# Soldier_Tracking.net
KiCad netlist of a schematic drawn in EAGLE
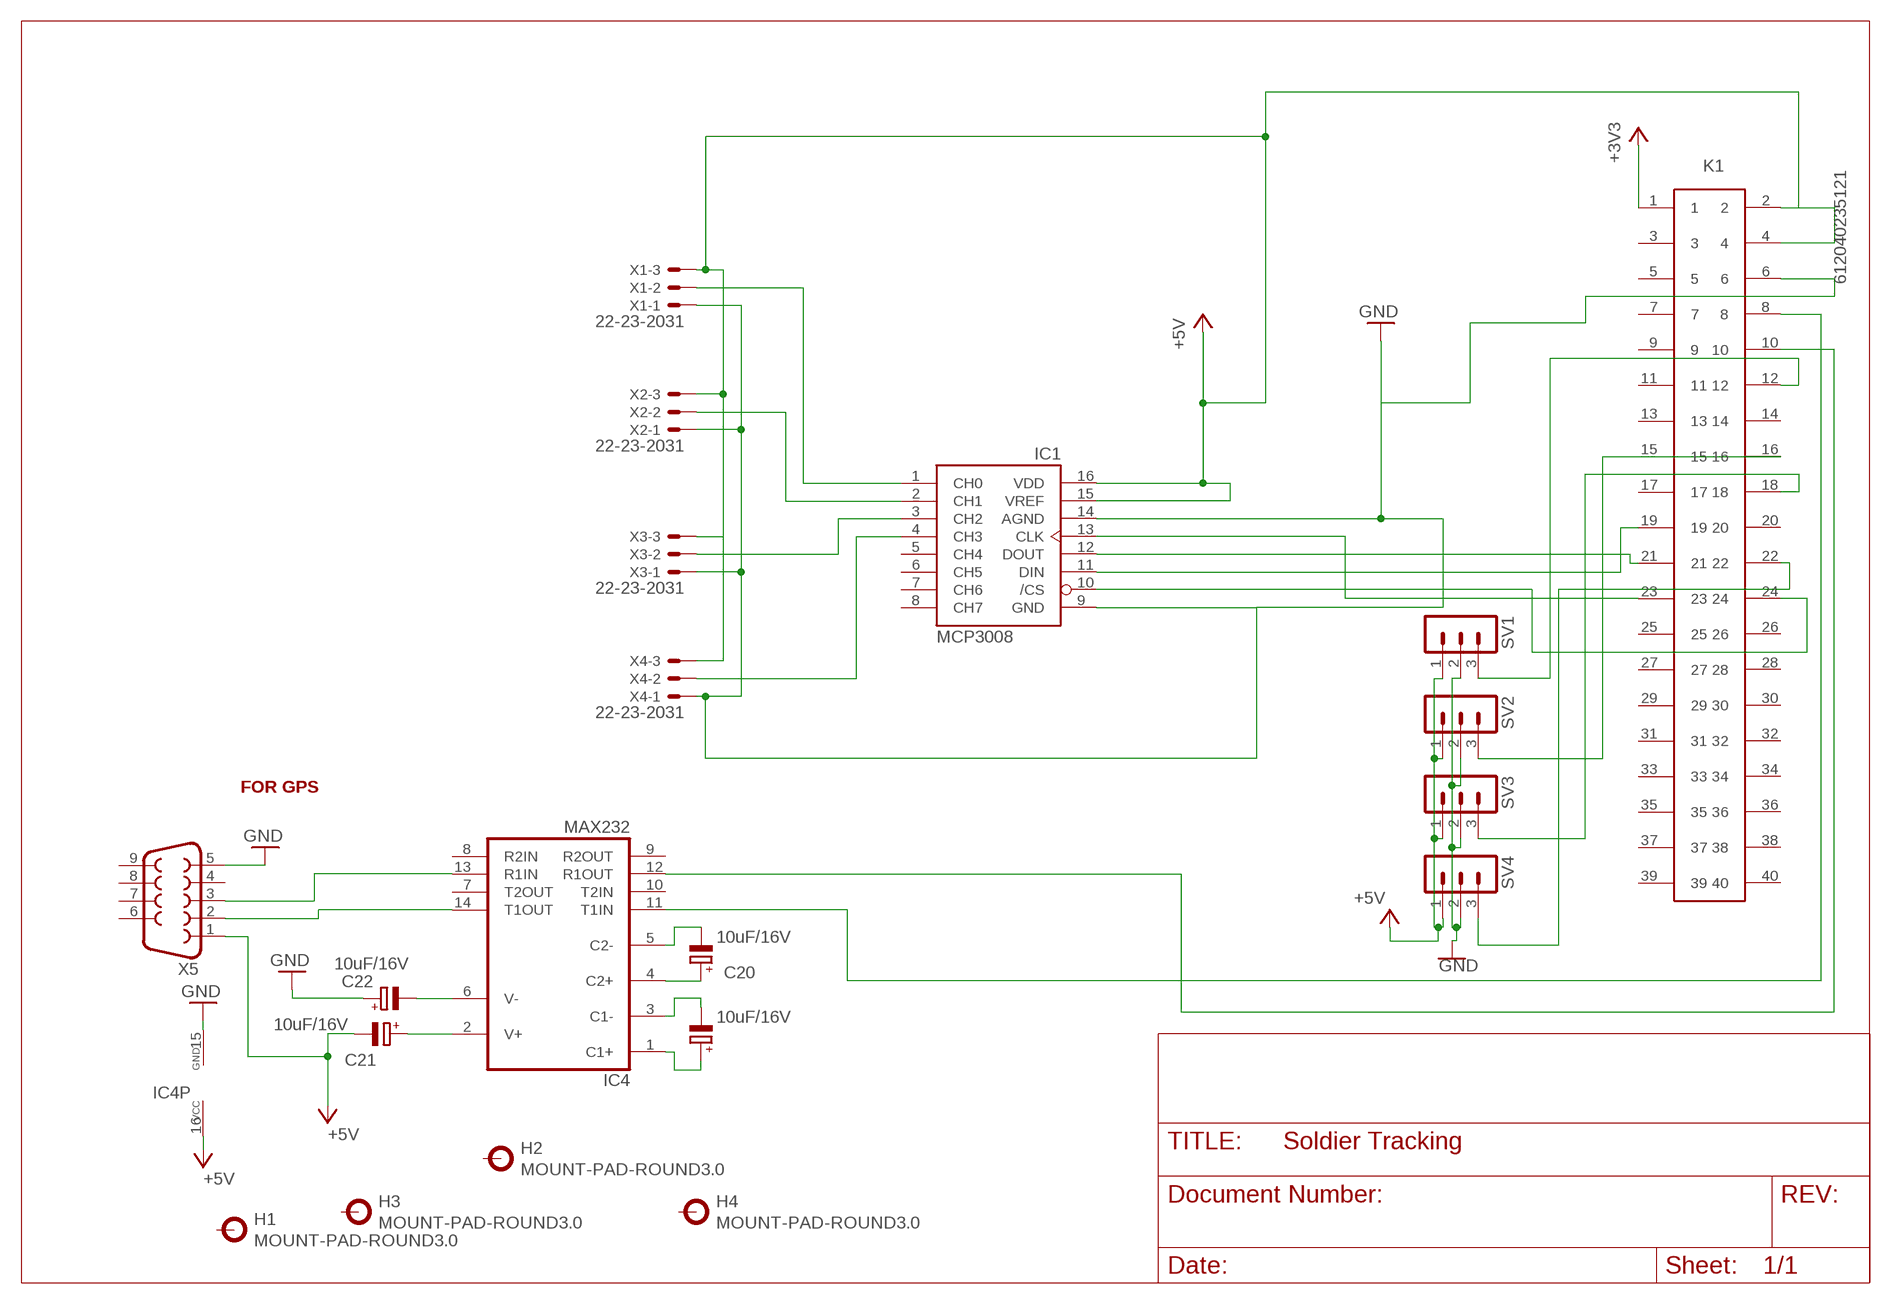
[diagram p0: schematic, sheet 1]

(export (version "E")
  (design (tool "Eeschema 10.0.6"))
  (components
    (comp (ref "C17")
      (value "10uF/16V")
      (footprint "eagle-import:E2,5-6")
      (libsource (lib "eagle-import") (part "CPOL-EUE2.5-6"))
    )
    (comp (ref "C20")
      (value "10uF/16V")
      (footprint "eagle-import:E2,5-6")
      (libsource (lib "eagle-import") (part "CPOL-EUE2.5-6"))
    )
    (comp (ref "C21")
      (value "10uF/16V")
      (footprint "eagle-import:E2,5-6")
      (libsource (lib "eagle-import") (part "CPOL-EUE2.5-6"))
    )
    (comp (ref "C22")
      (value "10uF/16V")
      (footprint "eagle-import:E2,5-6")
      (libsource (lib "eagle-import") (part "CPOL-EUE2.5-6"))
    )
    (comp (ref "H1")
      (value "MOUNT-PAD-ROUND3.0")
      (footprint "eagle-import:3,0-PAD")
      (libsource (lib "eagle-import") (part "MOUNT-PAD-ROUND3.0"))
    )
    (comp (ref "H2")
      (value "MOUNT-PAD-ROUND3.0")
      (footprint "eagle-import:3,0-PAD")
      (libsource (lib "eagle-import") (part "MOUNT-PAD-ROUND3.0"))
    )
    (comp (ref "H3")
      (value "MOUNT-PAD-ROUND3.0")
      (footprint "eagle-import:3,0-PAD")
      (libsource (lib "eagle-import") (part "MOUNT-PAD-ROUND3.0"))
    )
    (comp (ref "H4")
      (value "MOUNT-PAD-ROUND3.0")
      (footprint "eagle-import:3,0-PAD")
      (libsource (lib "eagle-import") (part "MOUNT-PAD-ROUND3.0"))
    )
    (comp (ref "IC1")
      (value "MCP3008")
      (footprint "eagle-import:DIL16")
      (libsource (lib "eagle-import") (part "MCP3008"))
    )
    (comp (ref "IC4")
      (value "MAX232")
      (footprint "eagle-import:DIL16")
      (libsource (lib "eagle-import") (part "MAX232"))
    )
    (comp (ref "K1")
      (value "612040235121")
      (footprint "eagle-import:612040235121")
      (libsource (lib "eagle-import") (part "612040235121"))
    )
    (comp (ref "SV1")
      (value "MA03-1")
      (footprint "eagle-import:MA03-1")
      (libsource (lib "eagle-import") (part "MA03-1"))
    )
    (comp (ref "SV2")
      (value "MA03-1")
      (footprint "eagle-import:MA03-1")
      (libsource (lib "eagle-import") (part "MA03-1"))
    )
    (comp (ref "SV3")
      (value "MA03-1")
      (footprint "eagle-import:MA03-1")
      (libsource (lib "eagle-import") (part "MA03-1"))
    )
    (comp (ref "SV4")
      (value "MA03-1")
      (footprint "eagle-import:MA03-1")
      (libsource (lib "eagle-import") (part "MA03-1"))
    )
    (comp (ref "X1")
      (value "22-23-2031")
      (footprint "eagle-import:22-23-2031")
      (fields (field (name "MF") "MOLEX"))
      (libsource (lib "eagle-import") (part "22-23-2031"))
    )
    (comp (ref "X2")
      (value "22-23-2031")
      (footprint "eagle-import:22-23-2031")
      (fields (field (name "MF") "MOLEX"))
      (libsource (lib "eagle-import") (part "22-23-2031"))
    )
    (comp (ref "X3")
      (value "22-23-2031")
      (footprint "eagle-import:22-23-2031")
      (fields (field (name "MF") "MOLEX"))
      (libsource (lib "eagle-import") (part "22-23-2031"))
    )
    (comp (ref "X4")
      (value "22-23-2031")
      (footprint "eagle-import:22-23-2031")
      (fields (field (name "MF") "MOLEX"))
      (libsource (lib "eagle-import") (part "22-23-2031"))
    )
    (comp (ref "X5")
      (value "F09HP")
      (footprint "eagle-import:F09HP")
      (libsource (lib "eagle-import") (part "F09HP"))
    )
  )
  (nets
    (net (code "1") (name "+3V3") (class "Default")
      (node (ref "K1") (pin "1") (pinfunction "1_1") (pintype "passive"))
    )
    (net (code "2") (name "+5V") (class "Default")
      (node (ref "C21") (pin "-") (pinfunction "-_-") (pintype "passive"))
      (node (ref "IC1") (pin "15") (pinfunction "VREF_15") (pintype "input"))
      (node (ref "IC1") (pin "16") (pinfunction "VDD_16") (pintype "power_in"))
      (node (ref "IC4") (pin "16") (pinfunction "VCC_16") (pintype "power_in"))
      (node (ref "K1") (pin "2") (pinfunction "2_2") (pintype "passive"))
      (node (ref "K1") (pin "4") (pinfunction "4_4") (pintype "passive"))
      (node (ref "SV1") (pin "1") (pinfunction "1_1") (pintype "passive"))
      (node (ref "SV2") (pin "1") (pinfunction "1_1") (pintype "passive"))
      (node (ref "SV3") (pin "1") (pinfunction "1_1") (pintype "passive"))
      (node (ref "SV4") (pin "1") (pinfunction "1_1") (pintype "passive"))
      (node (ref "X1") (pin "3") (pinfunction "S_3") (pintype "passive"))
      (node (ref "X2") (pin "3") (pinfunction "S_3") (pintype "passive"))
      (node (ref "X3") (pin "3") (pinfunction "S_3") (pintype "passive"))
      (node (ref "X4") (pin "3") (pinfunction "S_3") (pintype "passive"))
      (node (ref "X5") (pin "1") (pinfunction "1_1") (pintype "passive"))
    )
    (net (code "3") (name "GND") (class "Default")
      (node (ref "C22") (pin "+") (pinfunction "+_+") (pintype "passive"))
      (node (ref "IC1") (pin "14") (pinfunction "AGND_14") (pintype "power_in"))
      (node (ref "IC1") (pin "9") (pinfunction "GND_9") (pintype "power_in"))
      (node (ref "IC4") (pin "15") (pinfunction "GND_15") (pintype "power_in"))
      (node (ref "K1") (pin "6") (pinfunction "6_6") (pintype "passive"))
      (node (ref "SV1") (pin "2") (pinfunction "2_2") (pintype "passive"))
      (node (ref "SV2") (pin "2") (pinfunction "2_2") (pintype "passive"))
      (node (ref "SV3") (pin "2") (pinfunction "2_2") (pintype "passive"))
      (node (ref "SV4") (pin "2") (pinfunction "2_2") (pintype "passive"))
      (node (ref "X1") (pin "1") (pinfunction "S_1") (pintype "passive"))
      (node (ref "X2") (pin "1") (pinfunction "S_1") (pintype "passive"))
      (node (ref "X3") (pin "1") (pinfunction "S_1") (pintype "passive"))
      (node (ref "X4") (pin "1") (pinfunction "S_1") (pintype "passive"))
      (node (ref "X5") (pin "5") (pinfunction "5_5") (pintype "passive"))
    )
    (net (code "4") (name "Net-(IC1-CH0)") (class "Default")
      (node (ref "IC1") (pin "1") (pinfunction "CH0_1") (pintype "input"))
      (node (ref "X1") (pin "2") (pinfunction "S_2") (pintype "passive"))
    )
    (net (code "5") (name "Net-(IC1-CH1)") (class "Default")
      (node (ref "IC1") (pin "2") (pinfunction "CH1_2") (pintype "input"))
      (node (ref "X2") (pin "2") (pinfunction "S_2") (pintype "passive"))
    )
    (net (code "6") (name "Net-(IC1-CH2)") (class "Default")
      (node (ref "IC1") (pin "3") (pinfunction "CH2_3") (pintype "input"))
      (node (ref "X3") (pin "2") (pinfunction "S_2") (pintype "passive"))
    )
    (net (code "7") (name "Net-(IC1-CH3)") (class "Default")
      (node (ref "IC1") (pin "4") (pinfunction "CH3_4") (pintype "input"))
      (node (ref "X4") (pin "2") (pinfunction "S_2") (pintype "passive"))
    )
    (net (code "8") (name "Net-(IC1-CLK)") (class "Default")
      (node (ref "IC1") (pin "13") (pinfunction "CLK_13") (pintype "input"))
      (node (ref "K1") (pin "23") (pinfunction "23_23") (pintype "passive"))
    )
    (net (code "9") (name "Net-(IC1-DIN)") (class "Default")
      (node (ref "IC1") (pin "11") (pinfunction "DIN_11") (pintype "input"))
      (node (ref "K1") (pin "19") (pinfunction "19_19") (pintype "passive"))
    )
    (net (code "10") (name "Net-(IC1-DOUT)") (class "Default")
      (node (ref "IC1") (pin "12") (pinfunction "DOUT_12") (pintype "output"))
      (node (ref "K1") (pin "21") (pinfunction "21_21") (pintype "passive"))
    )
    (net (code "11") (name "Net-(IC1-{slash}CS)") (class "Default")
      (node (ref "IC1") (pin "10") (pinfunction "/CS_10") (pintype "input"))
      (node (ref "K1") (pin "24") (pinfunction "24_24") (pintype "passive"))
    )
    (net (code "12") (name "Net-(IC4A-C1+)") (class "Default")
      (node (ref "C17") (pin "+") (pinfunction "+_+") (pintype "passive"))
      (node (ref "IC4") (pin "1") (pinfunction "C1+_1") (pintype "bidirectional"))
    )
    (net (code "13") (name "Net-(IC4A-C1-)") (class "Default")
      (node (ref "C17") (pin "-") (pinfunction "-_-") (pintype "passive"))
      (node (ref "IC4") (pin "3") (pinfunction "C1-_3") (pintype "bidirectional"))
    )
    (net (code "14") (name "Net-(IC4A-C2+)") (class "Default")
      (node (ref "C20") (pin "+") (pinfunction "+_+") (pintype "passive"))
      (node (ref "IC4") (pin "4") (pinfunction "C2+_4") (pintype "bidirectional"))
    )
    (net (code "15") (name "Net-(IC4A-C2-)") (class "Default")
      (node (ref "C20") (pin "-") (pinfunction "-_-") (pintype "passive"))
      (node (ref "IC4") (pin "5") (pinfunction "C2-_5") (pintype "bidirectional"))
    )
    (net (code "16") (name "Net-(IC4A-R1IN)") (class "Default")
      (node (ref "IC4") (pin "13") (pinfunction "R1IN_13") (pintype "input"))
      (node (ref "X5") (pin "3") (pinfunction "3_3") (pintype "passive"))
    )
    (net (code "17") (name "Net-(IC4A-R1OUT)") (class "Default")
      (node (ref "IC4") (pin "12") (pinfunction "R1OUT_12") (pintype "output"))
      (node (ref "K1") (pin "10") (pinfunction "10_10") (pintype "passive"))
    )
    (net (code "18") (name "Net-(IC4A-T1IN)") (class "Default")
      (node (ref "IC4") (pin "11") (pinfunction "T1IN_11") (pintype "input"))
      (node (ref "K1") (pin "8") (pinfunction "8_8") (pintype "passive"))
    )
    (net (code "19") (name "Net-(IC4A-T1OUT)") (class "Default")
      (node (ref "IC4") (pin "14") (pinfunction "T1OUT_14") (pintype "output"))
      (node (ref "X5") (pin "2") (pinfunction "2_2") (pintype "passive"))
    )
    (net (code "20") (name "Net-(IC4A-V+)") (class "Default")
      (node (ref "C21") (pin "+") (pinfunction "+_+") (pintype "passive"))
      (node (ref "IC4") (pin "2") (pinfunction "V+_2") (pintype "bidirectional"))
    )
    (net (code "21") (name "Net-(IC4A-V-)") (class "Default")
      (node (ref "C22") (pin "-") (pinfunction "-_-") (pintype "passive"))
      (node (ref "IC4") (pin "6") (pinfunction "V-_6") (pintype "bidirectional"))
    )
    (net (code "22") (name "Net-(K1-Pad12)") (class "Default")
      (node (ref "K1") (pin "12") (pinfunction "12_12") (pintype "passive"))
      (node (ref "SV1") (pin "3") (pinfunction "3_3") (pintype "passive"))
    )
    (net (code "23") (name "Net-(K1-Pad16)") (class "Default")
      (node (ref "K1") (pin "16") (pinfunction "16_16") (pintype "passive"))
      (node (ref "SV2") (pin "3") (pinfunction "3_3") (pintype "passive"))
    )
    (net (code "24") (name "Net-(K1-Pad18)") (class "Default")
      (node (ref "K1") (pin "18") (pinfunction "18_18") (pintype "passive"))
      (node (ref "SV3") (pin "3") (pinfunction "3_3") (pintype "passive"))
    )
    (net (code "25") (name "Net-(K1-Pad22)") (class "Default")
      (node (ref "K1") (pin "22") (pinfunction "22_22") (pintype "passive"))
      (node (ref "SV4") (pin "3") (pinfunction "3_3") (pintype "passive"))
    )
    (net (code "26") (name "unconnected-(H1-MOUNT-PadB3,0)") (class "Default")
      (node (ref "H1") (pin "B3,0") (pinfunction "MOUNT_B3,0") (pintype "passive"))
    )
    (net (code "27") (name "unconnected-(H2-MOUNT-PadB3,0)") (class "Default")
      (node (ref "H2") (pin "B3,0") (pinfunction "MOUNT_B3,0") (pintype "passive"))
    )
    (net (code "28") (name "unconnected-(H3-MOUNT-PadB3,0)") (class "Default")
      (node (ref "H3") (pin "B3,0") (pinfunction "MOUNT_B3,0") (pintype "passive"))
    )
    (net (code "29") (name "unconnected-(H4-MOUNT-PadB3,0)") (class "Default")
      (node (ref "H4") (pin "B3,0") (pinfunction "MOUNT_B3,0") (pintype "passive"))
    )
    (net (code "30") (name "unconnected-(IC1-CH4-Pad5)") (class "Default")
      (node (ref "IC1") (pin "5") (pinfunction "CH4_5") (pintype "input"))
    )
    (net (code "31") (name "unconnected-(IC1-CH5-Pad6)") (class "Default")
      (node (ref "IC1") (pin "6") (pinfunction "CH5_6") (pintype "input"))
    )
    (net (code "32") (name "unconnected-(IC1-CH6-Pad7)") (class "Default")
      (node (ref "IC1") (pin "7") (pinfunction "CH6_7") (pintype "input"))
    )
    (net (code "33") (name "unconnected-(IC1-CH7-Pad8)") (class "Default")
      (node (ref "IC1") (pin "8") (pinfunction "CH7_8") (pintype "input"))
    )
    (net (code "34") (name "unconnected-(IC4A-R2IN-Pad8)") (class "Default")
      (node (ref "IC4") (pin "8") (pinfunction "R2IN_8") (pintype "input"))
    )
    (net (code "35") (name "unconnected-(IC4A-R2OUT-Pad9)") (class "Default")
      (node (ref "IC4") (pin "9") (pinfunction "R2OUT_9") (pintype "output"))
    )
    (net (code "36") (name "unconnected-(IC4A-T2IN-Pad10)") (class "Default")
      (node (ref "IC4") (pin "10") (pinfunction "T2IN_10") (pintype "input"))
    )
    (net (code "37") (name "unconnected-(IC4A-T2OUT-Pad7)") (class "Default")
      (node (ref "IC4") (pin "7") (pinfunction "T2OUT_7") (pintype "output"))
    )
    (net (code "38") (name "unconnected-(K1-Pad3)") (class "Default")
      (node (ref "K1") (pin "3") (pinfunction "3_3") (pintype "passive"))
    )
    (net (code "39") (name "unconnected-(K1-Pad5)") (class "Default")
      (node (ref "K1") (pin "5") (pinfunction "5_5") (pintype "passive"))
    )
    (net (code "40") (name "unconnected-(K1-Pad7)") (class "Default")
      (node (ref "K1") (pin "7") (pinfunction "7_7") (pintype "passive"))
    )
    (net (code "41") (name "unconnected-(K1-Pad9)") (class "Default")
      (node (ref "K1") (pin "9") (pinfunction "9_9") (pintype "passive"))
    )
    (net (code "42") (name "unconnected-(K1-Pad11)") (class "Default")
      (node (ref "K1") (pin "11") (pinfunction "11_11") (pintype "passive"))
    )
    (net (code "43") (name "unconnected-(K1-Pad13)") (class "Default")
      (node (ref "K1") (pin "13") (pinfunction "13_13") (pintype "passive"))
    )
    (net (code "44") (name "unconnected-(K1-Pad14)") (class "Default")
      (node (ref "K1") (pin "14") (pinfunction "14_14") (pintype "passive"))
    )
    (net (code "45") (name "unconnected-(K1-Pad15)") (class "Default")
      (node (ref "K1") (pin "15") (pinfunction "15_15") (pintype "passive"))
    )
    (net (code "46") (name "unconnected-(K1-Pad17)") (class "Default")
      (node (ref "K1") (pin "17") (pinfunction "17_17") (pintype "passive"))
    )
    (net (code "47") (name "unconnected-(K1-Pad20)") (class "Default")
      (node (ref "K1") (pin "20") (pinfunction "20_20") (pintype "passive"))
    )
    (net (code "48") (name "unconnected-(K1-Pad25)") (class "Default")
      (node (ref "K1") (pin "25") (pinfunction "25_25") (pintype "passive"))
    )
    (net (code "49") (name "unconnected-(K1-Pad26)") (class "Default")
      (node (ref "K1") (pin "26") (pinfunction "26_26") (pintype "passive"))
    )
    (net (code "50") (name "unconnected-(K1-Pad27)") (class "Default")
      (node (ref "K1") (pin "27") (pinfunction "27_27") (pintype "passive"))
    )
    (net (code "51") (name "unconnected-(K1-Pad28)") (class "Default")
      (node (ref "K1") (pin "28") (pinfunction "28_28") (pintype "passive"))
    )
    (net (code "52") (name "unconnected-(K1-Pad29)") (class "Default")
      (node (ref "K1") (pin "29") (pinfunction "29_29") (pintype "passive"))
    )
    (net (code "53") (name "unconnected-(K1-Pad30)") (class "Default")
      (node (ref "K1") (pin "30") (pinfunction "30_30") (pintype "passive"))
    )
    (net (code "54") (name "unconnected-(K1-Pad31)") (class "Default")
      (node (ref "K1") (pin "31") (pinfunction "31_31") (pintype "passive"))
    )
    (net (code "55") (name "unconnected-(K1-Pad32)") (class "Default")
      (node (ref "K1") (pin "32") (pinfunction "32_32") (pintype "passive"))
    )
    (net (code "56") (name "unconnected-(K1-Pad33)") (class "Default")
      (node (ref "K1") (pin "33") (pinfunction "33_33") (pintype "passive"))
    )
    (net (code "57") (name "unconnected-(K1-Pad34)") (class "Default")
      (node (ref "K1") (pin "34") (pinfunction "34_34") (pintype "passive"))
    )
    (net (code "58") (name "unconnected-(K1-Pad35)") (class "Default")
      (node (ref "K1") (pin "35") (pinfunction "35_35") (pintype "passive"))
    )
    (net (code "59") (name "unconnected-(K1-Pad36)") (class "Default")
      (node (ref "K1") (pin "36") (pinfunction "36_36") (pintype "passive"))
    )
    (net (code "60") (name "unconnected-(K1-Pad37)") (class "Default")
      (node (ref "K1") (pin "37") (pinfunction "37_37") (pintype "passive"))
    )
    (net (code "61") (name "unconnected-(K1-Pad38)") (class "Default")
      (node (ref "K1") (pin "38") (pinfunction "38_38") (pintype "passive"))
    )
    (net (code "62") (name "unconnected-(K1-Pad39)") (class "Default")
      (node (ref "K1") (pin "39") (pinfunction "39_39") (pintype "passive"))
    )
    (net (code "63") (name "unconnected-(K1-Pad40)") (class "Default")
      (node (ref "K1") (pin "40") (pinfunction "40_40") (pintype "passive"))
    )
    (net (code "64") (name "unconnected-(X5-Pad4)") (class "Default")
      (node (ref "X5") (pin "4") (pinfunction "4_4") (pintype "passive"))
    )
    (net (code "65") (name "unconnected-(X5-Pad6)") (class "Default")
      (node (ref "X5") (pin "6") (pinfunction "6_6") (pintype "passive"))
    )
    (net (code "66") (name "unconnected-(X5-Pad7)") (class "Default")
      (node (ref "X5") (pin "7") (pinfunction "7_7") (pintype "passive"))
    )
    (net (code "67") (name "unconnected-(X5-Pad8)") (class "Default")
      (node (ref "X5") (pin "8") (pinfunction "8_8") (pintype "passive"))
    )
    (net (code "68") (name "unconnected-(X5-Pad9)") (class "Default")
      (node (ref "X5") (pin "9") (pinfunction "9_9") (pintype "passive"))
    )
  )
)
